# breakout_v2.net
KiCad netlist of a schematic drawn in EAGLE
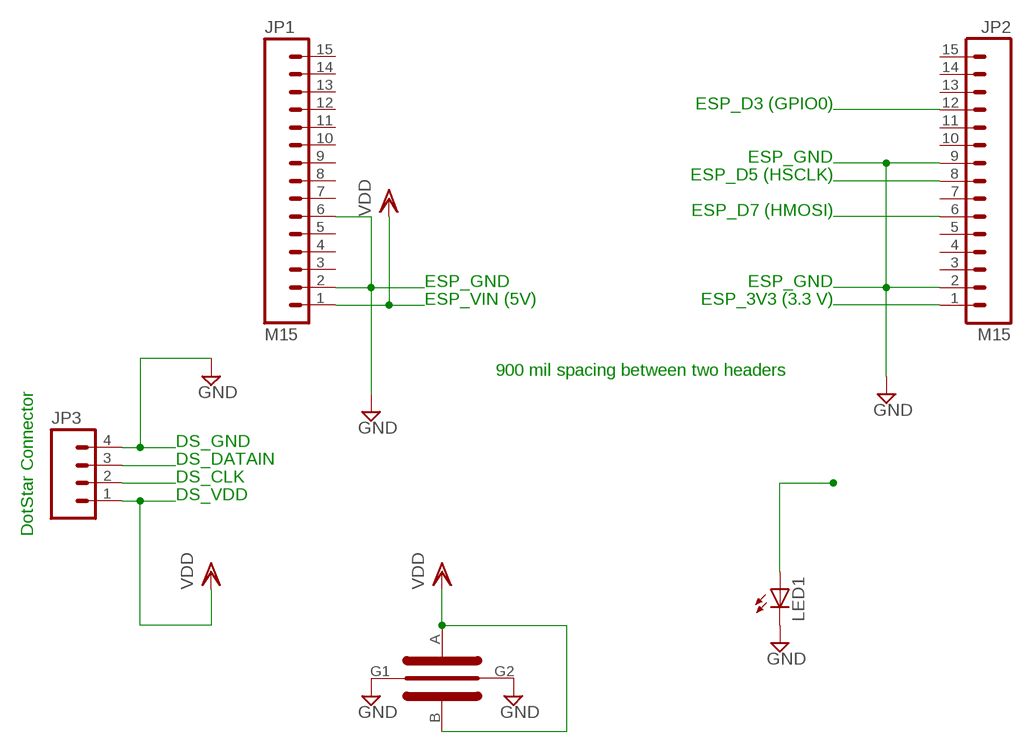
[diagram p0: schematic, sheet 1]

(export (version "E")
  (design (tool "Eeschema 10.0.6"))
  (components
    (comp (ref "JP1")
      (value "M15")
      (footprint "eagle-import:1X15")
      (libsource (lib "eagle-import") (part "M15"))
    )
    (comp (ref "JP2")
      (value "M15")
      (footprint "eagle-import:1X15")
      (libsource (lib "eagle-import") (part "M15"))
    )
    (comp (ref "JP3")
      (value "M04PTH")
      (footprint "eagle-import:1X04")
      (libsource (lib "eagle-import") (part "M04PTH"))
    )
    (comp (ref "LED1")
      (value "LED5MM")
      (footprint "eagle-import:LED5MM")
      (libsource (lib "eagle-import") (part "LED5MM"))
    )
    (comp (ref "U$1")
      (value "X2Y_CAP")
      (footprint "eagle-import:0603(X14)")
      (libsource (lib "eagle-import") (part "X2Y_CAP"))
    )
  )
  (nets
    (net (code "1") (name "/DS_CLK") (class "Default")
      (node (ref "JP2") (pin "8") (pinfunction "8_8") (pintype "passive"))
      (node (ref "JP3") (pin "2") (pinfunction "2_2") (pintype "passive"))
    )
    (net (code "2") (name "/DS_DATAIN") (class "Default")
      (node (ref "JP2") (pin "6") (pinfunction "6_6") (pintype "passive"))
      (node (ref "JP3") (pin "3") (pinfunction "3_3") (pintype "passive"))
    )
    (net (code "3") (name "/LED_PIN") (class "Default")
      (node (ref "JP2") (pin "12") (pinfunction "12_12") (pintype "passive"))
      (node (ref "LED1") (pin "A") (pinfunction "A_A") (pintype "passive"))
    )
    (net (code "4") (name "GND") (class "Default")
      (node (ref "JP1") (pin "2") (pinfunction "2_2") (pintype "passive"))
      (node (ref "JP1") (pin "6") (pinfunction "6_6") (pintype "passive"))
      (node (ref "JP2") (pin "2") (pinfunction "2_2") (pintype "passive"))
      (node (ref "JP2") (pin "9") (pinfunction "9_9") (pintype "passive"))
      (node (ref "JP3") (pin "4") (pinfunction "4_4") (pintype "passive"))
      (node (ref "LED1") (pin "K") (pinfunction "C_K") (pintype "passive"))
      (node (ref "U$1") (pin "G1") (pinfunction "G1_G1") (pintype "bidirectional"))
      (node (ref "U$1") (pin "G2") (pinfunction "G2_G2") (pintype "bidirectional"))
    )
    (net (code "5") (name "VDD") (class "Default")
      (node (ref "JP1") (pin "1") (pinfunction "1_1") (pintype "passive"))
      (node (ref "JP3") (pin "1") (pinfunction "1_1") (pintype "passive"))
      (node (ref "U$1") (pin "A") (pinfunction "A_A") (pintype "bidirectional"))
      (node (ref "U$1") (pin "B") (pinfunction "B_B") (pintype "bidirectional"))
    )
    (net (code "6") (name "unconnected-(JP1-Pad3)") (class "Default")
      (node (ref "JP1") (pin "3") (pinfunction "3_3") (pintype "passive"))
    )
    (net (code "7") (name "unconnected-(JP1-Pad4)") (class "Default")
      (node (ref "JP1") (pin "4") (pinfunction "4_4") (pintype "passive"))
    )
    (net (code "8") (name "unconnected-(JP1-Pad5)") (class "Default")
      (node (ref "JP1") (pin "5") (pinfunction "5_5") (pintype "passive"))
    )
    (net (code "9") (name "unconnected-(JP1-Pad7)") (class "Default")
      (node (ref "JP1") (pin "7") (pinfunction "7_7") (pintype "passive"))
    )
    (net (code "10") (name "unconnected-(JP1-Pad8)") (class "Default")
      (node (ref "JP1") (pin "8") (pinfunction "8_8") (pintype "passive"))
    )
    (net (code "11") (name "unconnected-(JP1-Pad9)") (class "Default")
      (node (ref "JP1") (pin "9") (pinfunction "9_9") (pintype "passive"))
    )
    (net (code "12") (name "unconnected-(JP1-Pad10)") (class "Default")
      (node (ref "JP1") (pin "10") (pinfunction "10_10") (pintype "passive"))
    )
    (net (code "13") (name "unconnected-(JP1-Pad11)") (class "Default")
      (node (ref "JP1") (pin "11") (pinfunction "11_11") (pintype "passive"))
    )
    (net (code "14") (name "unconnected-(JP1-Pad12)") (class "Default")
      (node (ref "JP1") (pin "12") (pinfunction "12_12") (pintype "passive"))
    )
    (net (code "15") (name "unconnected-(JP1-Pad13)") (class "Default")
      (node (ref "JP1") (pin "13") (pinfunction "13_13") (pintype "passive"))
    )
    (net (code "16") (name "unconnected-(JP1-Pad14)") (class "Default")
      (node (ref "JP1") (pin "14") (pinfunction "14_14") (pintype "passive"))
    )
    (net (code "17") (name "unconnected-(JP1-Pad15)") (class "Default")
      (node (ref "JP1") (pin "15") (pinfunction "15_15") (pintype "passive"))
    )
    (net (code "18") (name "unconnected-(JP2-Pad1)") (class "Default")
      (node (ref "JP2") (pin "1") (pinfunction "1_1") (pintype "passive"))
    )
    (net (code "19") (name "unconnected-(JP2-Pad3)") (class "Default")
      (node (ref "JP2") (pin "3") (pinfunction "3_3") (pintype "passive"))
    )
    (net (code "20") (name "unconnected-(JP2-Pad4)") (class "Default")
      (node (ref "JP2") (pin "4") (pinfunction "4_4") (pintype "passive"))
    )
    (net (code "21") (name "unconnected-(JP2-Pad5)") (class "Default")
      (node (ref "JP2") (pin "5") (pinfunction "5_5") (pintype "passive"))
    )
    (net (code "22") (name "unconnected-(JP2-Pad7)") (class "Default")
      (node (ref "JP2") (pin "7") (pinfunction "7_7") (pintype "passive"))
    )
    (net (code "23") (name "unconnected-(JP2-Pad10)") (class "Default")
      (node (ref "JP2") (pin "10") (pinfunction "10_10") (pintype "passive"))
    )
    (net (code "24") (name "unconnected-(JP2-Pad11)") (class "Default")
      (node (ref "JP2") (pin "11") (pinfunction "11_11") (pintype "passive"))
    )
    (net (code "25") (name "unconnected-(JP2-Pad13)") (class "Default")
      (node (ref "JP2") (pin "13") (pinfunction "13_13") (pintype "passive"))
    )
    (net (code "26") (name "unconnected-(JP2-Pad14)") (class "Default")
      (node (ref "JP2") (pin "14") (pinfunction "14_14") (pintype "passive"))
    )
    (net (code "27") (name "unconnected-(JP2-Pad15)") (class "Default")
      (node (ref "JP2") (pin "15") (pinfunction "15_15") (pintype "passive"))
    )
  )
)
